# SOIC12-TSSOP12_v1_0.net
KiCad netlist of a schematic drawn in EAGLE
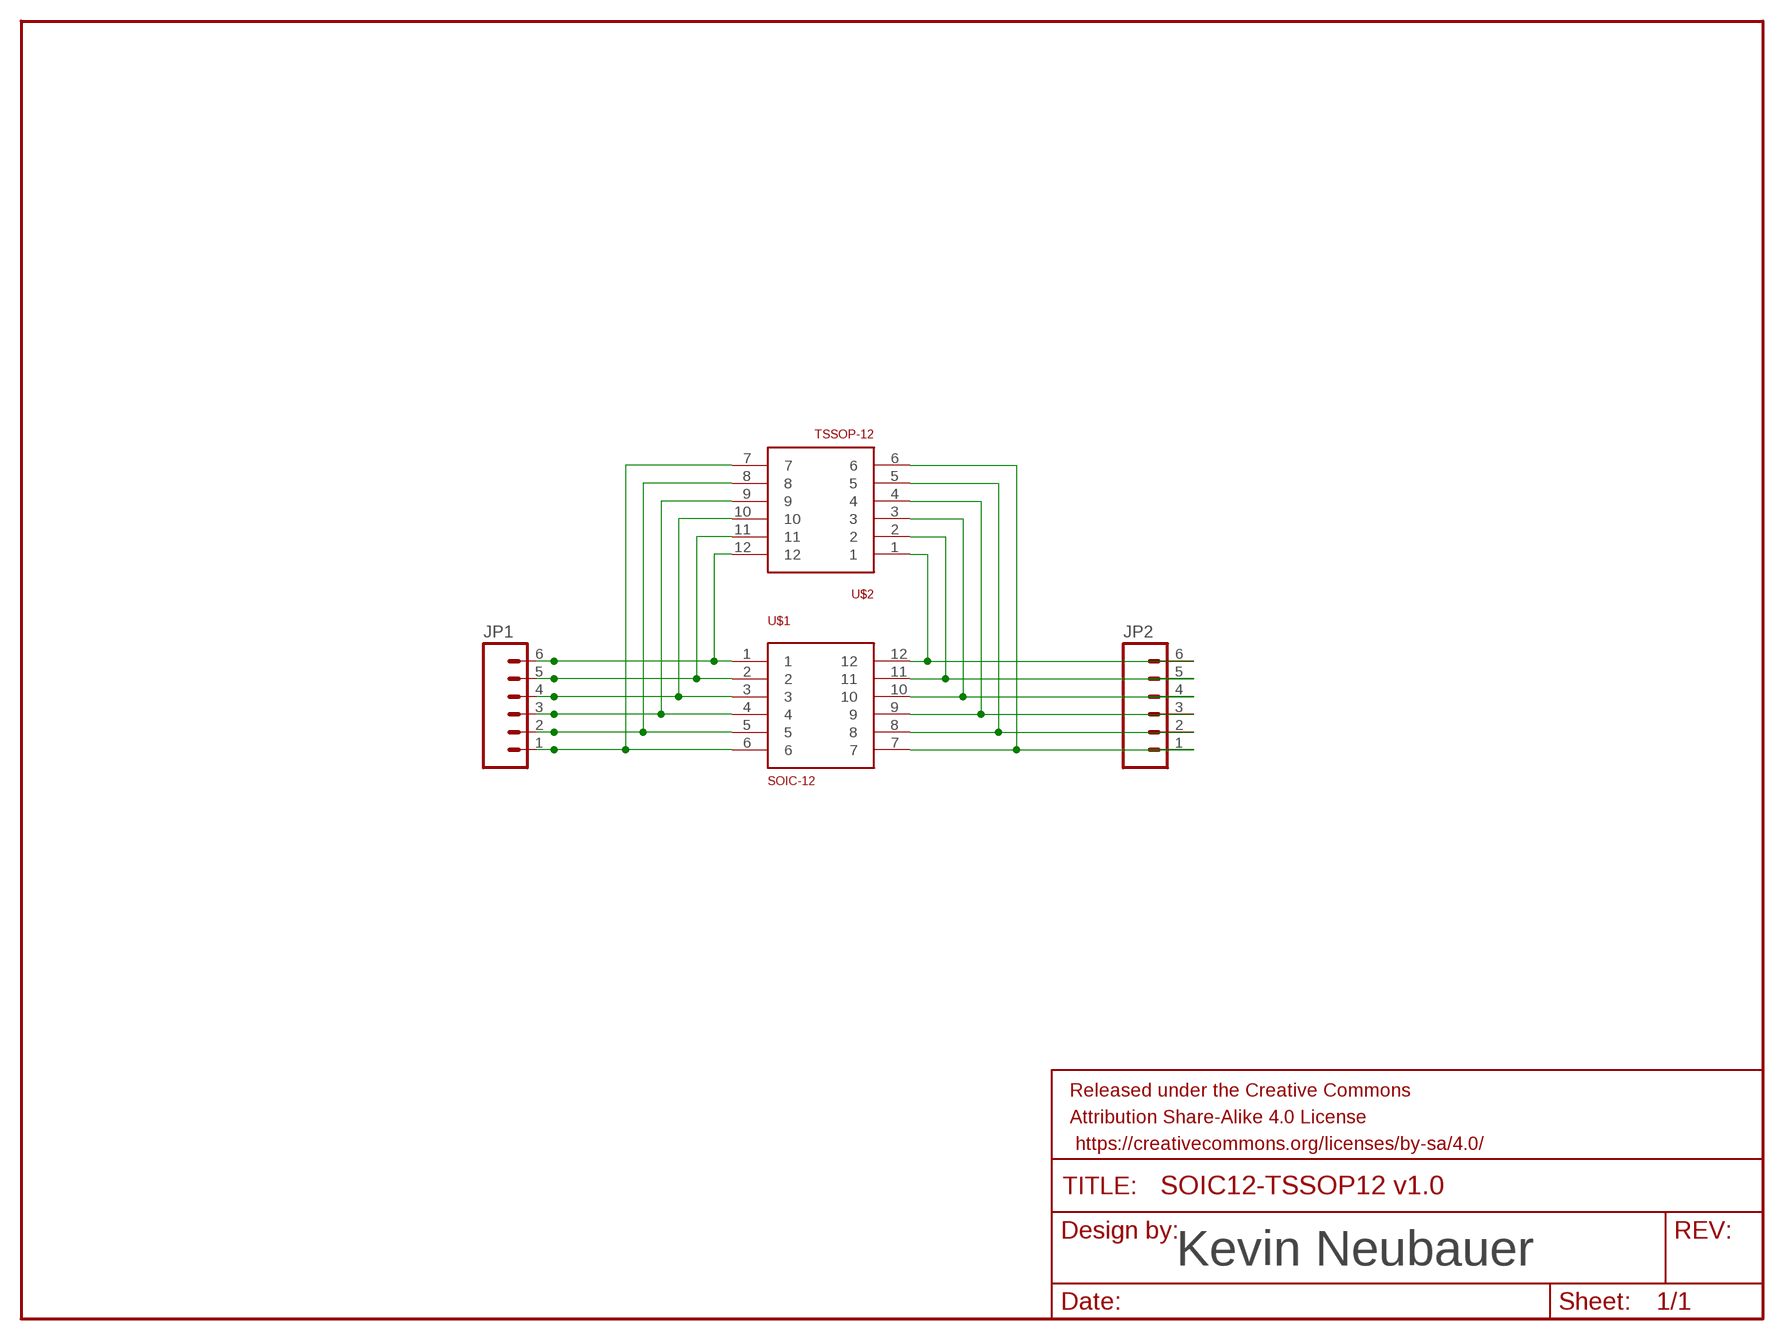
[diagram p0: schematic, sheet 1]

(export (version "E")
  (design (tool "Eeschema 10.0.6"))
  (components
    (comp (ref "FRAME1")
      (value "FRAME-LETTER")
      (footprint "eagle-import:CREATIVE_COMMONS")
      (libsource (lib "eagle-import") (part "FRAME-LETTER"))
    )
    (comp (ref "JP1")
      (value "M06NO_SILK")
      (footprint "eagle-import:1X06_NO_SILK")
      (libsource (lib "eagle-import") (part "M06NO_SILK"))
    )
    (comp (ref "JP2")
      (value "M06NO_SILK")
      (footprint "eagle-import:1X06_NO_SILK")
      (libsource (lib "eagle-import") (part "M06NO_SILK"))
    )
    (comp (ref "U$1")
      (value "SOIC-12")
      (footprint "eagle-import:SOIC-12")
      (libsource (lib "eagle-import") (part "SOIC-12"))
    )
    (comp (ref "U$2")
      (value "TSSOP-12")
      (footprint "eagle-import:TSSOP12")
      (libsource (lib "eagle-import") (part "TSSOP-12"))
    )
  )
  (nets
    (net (code "1") (name "Net-(JP1-Pad1)") (class "Default")
      (node (ref "JP1") (pin "1") (pinfunction "1_1") (pintype "passive"))
      (node (ref "U$1") (pin "6") (pinfunction "6_6") (pintype "bidirectional"))
      (node (ref "U$2") (pin "7") (pinfunction "7_7") (pintype "bidirectional"))
    )
    (net (code "2") (name "Net-(JP1-Pad2)") (class "Default")
      (node (ref "JP1") (pin "2") (pinfunction "2_2") (pintype "passive"))
      (node (ref "U$1") (pin "5") (pinfunction "5_5") (pintype "bidirectional"))
      (node (ref "U$2") (pin "8") (pinfunction "8_8") (pintype "bidirectional"))
    )
    (net (code "3") (name "Net-(JP1-Pad3)") (class "Default")
      (node (ref "JP1") (pin "3") (pinfunction "3_3") (pintype "passive"))
      (node (ref "U$1") (pin "4") (pinfunction "4_4") (pintype "bidirectional"))
      (node (ref "U$2") (pin "9") (pinfunction "9_9") (pintype "bidirectional"))
    )
    (net (code "4") (name "Net-(JP1-Pad4)") (class "Default")
      (node (ref "JP1") (pin "4") (pinfunction "4_4") (pintype "passive"))
      (node (ref "U$1") (pin "3") (pinfunction "3_3") (pintype "bidirectional"))
      (node (ref "U$2") (pin "10") (pinfunction "10_10") (pintype "bidirectional"))
    )
    (net (code "5") (name "Net-(JP1-Pad5)") (class "Default")
      (node (ref "JP1") (pin "5") (pinfunction "5_5") (pintype "passive"))
      (node (ref "U$1") (pin "2") (pinfunction "2_2") (pintype "bidirectional"))
      (node (ref "U$2") (pin "11") (pinfunction "11_11") (pintype "bidirectional"))
    )
    (net (code "6") (name "Net-(JP1-Pad6)") (class "Default")
      (node (ref "JP1") (pin "6") (pinfunction "6_6") (pintype "passive"))
      (node (ref "U$1") (pin "1") (pinfunction "1_1") (pintype "bidirectional"))
      (node (ref "U$2") (pin "12") (pinfunction "12_12") (pintype "bidirectional"))
    )
    (net (code "7") (name "Net-(JP2-Pad1)") (class "Default")
      (node (ref "JP2") (pin "1") (pinfunction "1_1") (pintype "passive"))
      (node (ref "U$1") (pin "7") (pinfunction "7_7") (pintype "bidirectional"))
      (node (ref "U$2") (pin "6") (pinfunction "6_6") (pintype "bidirectional"))
    )
    (net (code "8") (name "Net-(JP2-Pad2)") (class "Default")
      (node (ref "JP2") (pin "2") (pinfunction "2_2") (pintype "passive"))
      (node (ref "U$1") (pin "8") (pinfunction "8_8") (pintype "bidirectional"))
      (node (ref "U$2") (pin "5") (pinfunction "5_5") (pintype "bidirectional"))
    )
    (net (code "9") (name "Net-(JP2-Pad3)") (class "Default")
      (node (ref "JP2") (pin "3") (pinfunction "3_3") (pintype "passive"))
      (node (ref "U$1") (pin "9") (pinfunction "9_9") (pintype "bidirectional"))
      (node (ref "U$2") (pin "4") (pinfunction "4_4") (pintype "bidirectional"))
    )
    (net (code "10") (name "Net-(JP2-Pad4)") (class "Default")
      (node (ref "JP2") (pin "4") (pinfunction "4_4") (pintype "passive"))
      (node (ref "U$1") (pin "10") (pinfunction "10_10") (pintype "bidirectional"))
      (node (ref "U$2") (pin "3") (pinfunction "3_3") (pintype "bidirectional"))
    )
    (net (code "11") (name "Net-(JP2-Pad5)") (class "Default")
      (node (ref "JP2") (pin "5") (pinfunction "5_5") (pintype "passive"))
      (node (ref "U$1") (pin "11") (pinfunction "11_11") (pintype "bidirectional"))
      (node (ref "U$2") (pin "2") (pinfunction "2_2") (pintype "bidirectional"))
    )
    (net (code "12") (name "Net-(JP2-Pad6)") (class "Default")
      (node (ref "JP2") (pin "6") (pinfunction "6_6") (pintype "passive"))
      (node (ref "U$1") (pin "12") (pinfunction "12_12") (pintype "bidirectional"))
      (node (ref "U$2") (pin "1") (pinfunction "1_1") (pintype "bidirectional"))
    )
  )
)
